# SAM_E54_Xplained_Pro_Target_MCU.net
KiCad netlist of a schematic drawn in Altium Designer
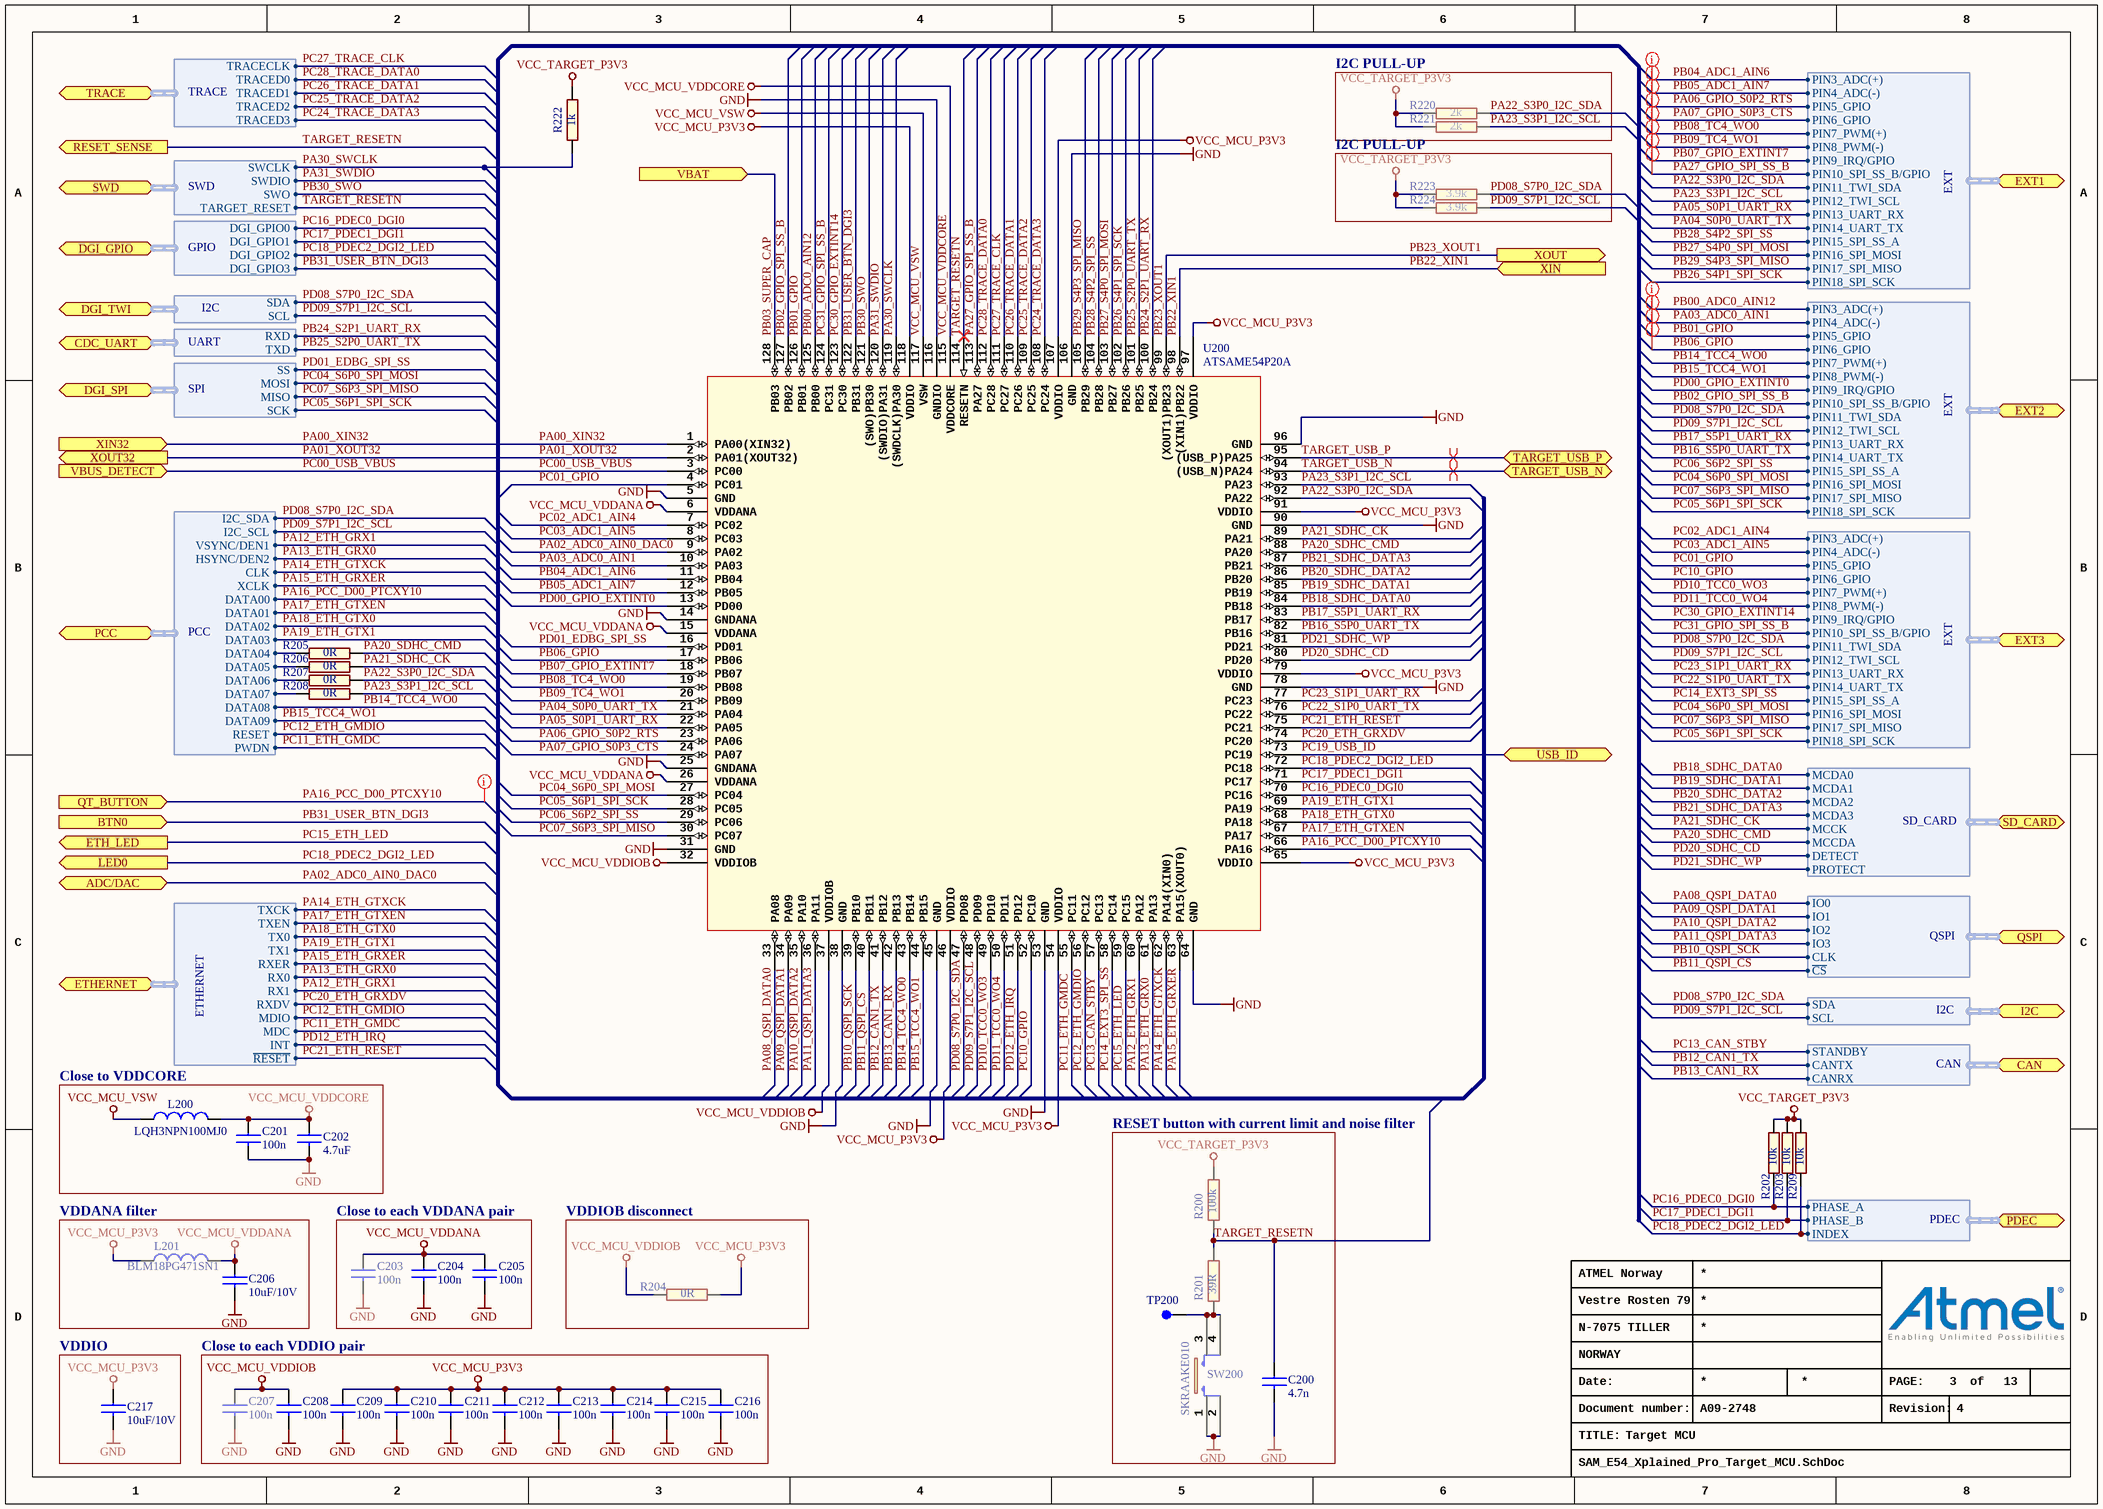
[diagram p0: SAM_E54_Xplained_Pro_Target_MCU.SchDoc]

(export (version "E")
  (design (tool "Eeschema 10.0.6"))
  (components
    (comp (ref "C200")
      (value "4.7n")
      (footprint "AP1-00053")
      (description "Ceramic capacitor, SMD 0402, X7R, 25V, +/-10% (de35287)")
      (fields (field (name "TOLERANCE") "25V, +/-10%") (field (name "MANUFACTURER") "PHYCOMP"))
      (libsource (lib "AltiumDbLib") (part "CAP-NONPOL"))
    )
    (comp (ref "C201")
      (value "100n")
      (footprint "AP1-00053")
      (description "Ceramic capacitor, SMD 0402, X7R, 16V, +/-10%")
      (fields (field (name "TOLERANCE") "16V, +/-10%") (field (name "MANUFACTURER") "Kemet"))
      (libsource (lib "AltiumDbLib") (part "CAP-NONPOL"))
    )
    (comp (ref "C202")
      (value "4.7uF")
      (footprint "AP1-00117")
      (description "Ceramic capacitor, SMD 0603, X5R, 10V, 10% (de31036)")
      (fields (field (name "TOLERANCE") "10%") (field (name "MANUFACTURER") "WALSIN Technology Corporation"))
      (libsource (lib "AltiumDbLib") (part "CAP-NONPOL"))
    )
    (comp (ref "C203")
      (value "100n")
      (footprint "AP1-00053")
      (description "Ceramic capacitor, SMD 0402, X7R, 16V, +/-10%")
      (fields (field (name "TOLERANCE") "16V, +/-10%") (field (name "MANUFACTURER") "Kemet"))
      (libsource (lib "AltiumDbLib") (part "CAP-NONPOL"))
    )
    (comp (ref "C204")
      (value "100n")
      (footprint "AP1-00053")
      (description "Ceramic capacitor, SMD 0402, X7R, 16V, +/-10%")
      (fields (field (name "TOLERANCE") "16V, +/-10%") (field (name "MANUFACTURER") "Kemet"))
      (libsource (lib "AltiumDbLib") (part "CAP-NONPOL"))
    )
    (comp (ref "C205")
      (value "100n")
      (footprint "AP1-00053")
      (description "Ceramic capacitor, SMD 0402, X7R, 16V, +/-10%")
      (fields (field (name "TOLERANCE") "16V, +/-10%") (field (name "MANUFACTURER") "Kemet"))
      (libsource (lib "AltiumDbLib") (part "CAP-NONPOL"))
    )
    (comp (ref "C206")
      (value "10uF/10V")
      (footprint "AP1-00117")
      (description "Ceramic capacitor, SMD 0603, X5R, 10V, 10UF Â± 20%")
      (fields (field (name "MANUFACTURER") "AVX") (field (name "MPN") "0603ZD106MAT2A"))
      (libsource (lib "AltiumDbLib") (part "CAP-NONPOL"))
    )
    (comp (ref "C207")
      (value "100n")
      (footprint "AP1-00053")
      (description "Ceramic capacitor, SMD 0402, X7R, 16V, +/-10%")
      (fields (field (name "TOLERANCE") "16V, +/-10%") (field (name "MANUFACTURER") "Kemet"))
      (libsource (lib "AltiumDbLib") (part "CAP-NONPOL"))
    )
    (comp (ref "C208")
      (value "100n")
      (footprint "AP1-00053")
      (description "Ceramic capacitor, SMD 0402, X7R, 16V, +/-10%")
      (fields (field (name "TOLERANCE") "16V, +/-10%") (field (name "MANUFACTURER") "Kemet"))
      (libsource (lib "AltiumDbLib") (part "CAP-NONPOL"))
    )
    (comp (ref "C209")
      (value "100n")
      (footprint "AP1-00053")
      (description "Ceramic capacitor, SMD 0402, X7R, 16V, +/-10%")
      (fields (field (name "TOLERANCE") "16V, +/-10%") (field (name "MANUFACTURER") "Kemet"))
      (libsource (lib "AltiumDbLib") (part "CAP-NONPOL"))
    )
    (comp (ref "C210")
      (value "100n")
      (footprint "AP1-00053")
      (description "Ceramic capacitor, SMD 0402, X7R, 16V, +/-10%")
      (fields (field (name "TOLERANCE") "16V, +/-10%") (field (name "MANUFACTURER") "Kemet"))
      (libsource (lib "AltiumDbLib") (part "CAP-NONPOL"))
    )
    (comp (ref "C211")
      (value "100n")
      (footprint "AP1-00053")
      (description "Ceramic capacitor, SMD 0402, X7R, 16V, +/-10%")
      (fields (field (name "TOLERANCE") "16V, +/-10%") (field (name "MANUFACTURER") "Kemet"))
      (libsource (lib "AltiumDbLib") (part "CAP-NONPOL"))
    )
    (comp (ref "C212")
      (value "100n")
      (footprint "AP1-00053")
      (description "Ceramic capacitor, SMD 0402, X7R, 16V, +/-10%")
      (fields (field (name "TOLERANCE") "16V, +/-10%") (field (name "MANUFACTURER") "Kemet"))
      (libsource (lib "AltiumDbLib") (part "CAP-NONPOL"))
    )
    (comp (ref "C213")
      (value "100n")
      (footprint "AP1-00053")
      (description "Ceramic capacitor, SMD 0402, X7R, 16V, +/-10%")
      (fields (field (name "TOLERANCE") "16V, +/-10%") (field (name "MANUFACTURER") "Kemet"))
      (libsource (lib "AltiumDbLib") (part "CAP-NONPOL"))
    )
    (comp (ref "C214")
      (value "100n")
      (footprint "AP1-00053")
      (description "Ceramic capacitor, SMD 0402, X7R, 16V, +/-10%")
      (fields (field (name "TOLERANCE") "16V, +/-10%") (field (name "MANUFACTURER") "Kemet"))
      (libsource (lib "AltiumDbLib") (part "CAP-NONPOL"))
    )
    (comp (ref "C215")
      (value "100n")
      (footprint "AP1-00053")
      (description "Ceramic capacitor, SMD 0402, X7R, 16V, +/-10%")
      (fields (field (name "TOLERANCE") "16V, +/-10%") (field (name "MANUFACTURER") "Kemet"))
      (libsource (lib "AltiumDbLib") (part "CAP-NONPOL"))
    )
    (comp (ref "C216")
      (value "100n")
      (footprint "AP1-00053")
      (description "Ceramic capacitor, SMD 0402, X7R, 16V, +/-10%")
      (fields (field (name "TOLERANCE") "16V, +/-10%") (field (name "MANUFACTURER") "Kemet"))
      (libsource (lib "AltiumDbLib") (part "CAP-NONPOL"))
    )
    (comp (ref "C217")
      (value "10uF/10V")
      (footprint "AP1-00117")
      (description "Ceramic capacitor, SMD 0603, X5R, 10V, 10UF Â± 20%")
      (fields (field (name "MANUFACTURER") "AVX") (field (name "MPN") "0603ZD106MAT2A"))
      (libsource (lib "AltiumDbLib") (part "CAP-NONPOL"))
    )
    (comp (ref "L200")
      (value "LQH3NPN100MJ0")
      (footprint "AP3-00115")
      (description "10uH power inductor, Isat = 560mA , Itemp = 710mA, Rdc = 0.360ohm")
      (fields (field (name "TOLERANCE") "Â±20%") (field (name "MANUFACTURER") "Murata"))
      (libsource (lib "AltiumDbLib") (part "INDUCTOR"))
    )
    (comp (ref "L201")
      (value "BLM18PG471SN1")
      (footprint "AP3-00005")
      (description "SMD RF inductor 0603. Z=470Ohm (@100MHz), Max R(dc)=0.65Ohm, Max current=1A")
      (fields (field (name "MANUFACTURER") "Murata"))
      (libsource (lib "AltiumDbLib") (part "INDUCTOR"))
    )
    (comp (ref "R200")
      (value "100k")
      (footprint "AP2-00011")
      (description "Thick film resistor, SMD 0402, 1/16W, 1%")
      (fields (field (name "TOLERANCE") "1 %") (field (name "MANUFACTURER") "ASJ"))
      (libsource (lib "AltiumDbLib") (part "R2"))
    )
    (comp (ref "R201")
      (value "39R")
      (footprint "AP2-00011")
      (description "Thick film resistor, SMD 0402, 1/16W, 1%")
      (fields (field (name "TOLERANCE") "1 %") (field (name "MANUFACTURER") "ASJ"))
      (libsource (lib "") (part "R2_3"))
    )
    (comp (ref "R202")
      (value "10k")
      (footprint "AP2-00011")
      (description "Thick film resistor, SMD 0402, 1/16W, 1%")
      (fields (field (name "TOLERANCE") "1 %") (field (name "MANUFACTURER") "vishay"))
      (libsource (lib "AltiumDbLib") (part "R2"))
    )
    (comp (ref "R203")
      (value "10k")
      (footprint "AP2-00011")
      (description "Thick film resistor, SMD 0402, 1/16W, 1%")
      (fields (field (name "TOLERANCE") "1 %") (field (name "MANUFACTURER") "vishay"))
      (libsource (lib "") (part "R2_2"))
    )
    (comp (ref "R204")
      (value "0R")
      (footprint "AP2-00000")
      (description "RES 0.0 OHM 1/16W 0402 SMD")
      (fields (field (name "TOLERANCE") "1 %") (field (name "MANUFACTURER") "(n/a)"))
      (libsource (lib "") (part "R2_1"))
    )
    (comp (ref "R205")
      (value "0R")
      (footprint "AP2-00000")
      (description "RES 0.0 OHM 1/16W 0402 SMD")
      (fields (field (name "TOLERANCE") "1 %") (field (name "MANUFACTURER") "(n/a)"))
      (libsource (lib "") (part "R2_1"))
    )
    (comp (ref "R206")
      (value "0R")
      (footprint "AP2-00000")
      (description "RES 0.0 OHM 1/16W 0402 SMD")
      (fields (field (name "TOLERANCE") "1 %") (field (name "MANUFACTURER") "(n/a)"))
      (libsource (lib "") (part "R2_1"))
    )
    (comp (ref "R207")
      (value "0R")
      (footprint "AP2-00000")
      (description "RES 0.0 OHM 1/16W 0402 SMD")
      (fields (field (name "TOLERANCE") "1 %") (field (name "MANUFACTURER") "(n/a)"))
      (libsource (lib "") (part "R2_1"))
    )
    (comp (ref "R208")
      (value "0R")
      (footprint "AP2-00000")
      (description "RES 0.0 OHM 1/16W 0402 SMD")
      (fields (field (name "TOLERANCE") "1 %") (field (name "MANUFACTURER") "(n/a)"))
      (libsource (lib "") (part "R2_1"))
    )
    (comp (ref "R209")
      (value "10k")
      (footprint "AP2-00011")
      (description "Thick film resistor, SMD 0402, 1/16W, 1%")
      (fields (field (name "TOLERANCE") "1 %") (field (name "MANUFACTURER") "vishay"))
      (libsource (lib "") (part "R2_2"))
    )
    (comp (ref "R220")
      (value "2k")
      (footprint "AP2-00011")
      (description "Thick film resistor, SMD 0402, 1/16W, 1%")
      (fields (field (name "TOLERANCE") "1 %"))
      (libsource (lib "") (part "R2_1"))
    )
    (comp (ref "R221")
      (value "2k")
      (footprint "AP2-00011")
      (description "Thick film resistor, SMD 0402, 1/16W, 1%")
      (fields (field (name "TOLERANCE") "1 %"))
      (libsource (lib "") (part "R2_1"))
    )
    (comp (ref "R222")
      (value "1k")
      (footprint "AP2-00011")
      (description "Thick film resistor, SMD 0402, 1/16W, 1%")
      (fields (field (name "TOLERANCE") "1 %") (field (name "MANUFACTURER") "ASJ"))
      (libsource (lib "AltiumDbLib") (part "R2"))
    )
    (comp (ref "R223")
      (value "3.9k")
      (footprint "AP2-00011")
      (description "Thick film resistor, SMD 0402, 1/16W, 1%")
      (fields (field (name "TOLERANCE") "1 %"))
      (libsource (lib "") (part "R2_1"))
    )
    (comp (ref "R224")
      (value "3.9k")
      (footprint "AP2-00011")
      (description "Thick film resistor, SMD 0402, 1/16W, 1%")
      (fields (field (name "TOLERANCE") "1 %"))
      (libsource (lib "") (part "R2_1"))
    )
    (comp (ref "SW200")
      (value "SKRAAKE010")
      (footprint "AP8-00137")
      (description "6.2x6.2 mm SMD tact switch, same as A08-0091 but less force is needed")
      (fields (field (name "MANUFACTURER") "ALPS"))
      (libsource (lib "AltiumDbLib") (part "PUSHBUTTON1"))
    )
    (comp (ref "TP200")
      (value "~")
      (footprint "AP8-00010")
      (description "Single SMD testpad")
      (libsource (lib "AltiumDbLib") (part "TESTPOINT"))
    )
    (comp (ref "U200")
      (value "ATSAME54P20A")
      (footprint "AP6-00477")
      (description "Atmel 32-bit RISC MCU")
      (fields (field (name "MANUFACTURER") "ATMEL") (field (name "MPN") "ATSAME54P20A-ANTES"))
      (libsource (lib "AltiumDbLib") (part "SAME54_TQFP128"))
    )
  )
  (nets
    (net (code "15") (name "/DATA04") (class "Default")
      (node (ref "R205") (pin "2") (pinfunction "2_2") (pintype "passive"))
    )
    (net (code "16") (name "/DATA05") (class "Default")
      (node (ref "R206") (pin "2") (pinfunction "2_2") (pintype "passive"))
    )
    (net (code "17") (name "/DATA06") (class "Default")
      (node (ref "R207") (pin "2") (pinfunction "2_2") (pintype "passive"))
    )
    (net (code "18") (name "/DATA07") (class "Default")
      (node (ref "R208") (pin "2") (pinfunction "2_2") (pintype "passive"))
    )
    (net (code "19") (name "/PA00_XIN32") (class "Default")
      (node (ref "U200") (pin "1") (pinfunction "PA00(XIN32)_1") (pintype "bidirectional"))
    )
    (net (code "20") (name "/PA01_XOUT32") (class "Default")
      (node (ref "U200") (pin "2") (pinfunction "PA01(XOUT32)_2") (pintype "bidirectional"))
    )
    (net (code "21") (name "/PA02_ADC0_AIN0_DAC0") (class "Default")
      (node (ref "U200") (pin "9") (pinfunction "PA02_9") (pintype "bidirectional"))
    )
    (net (code "22") (name "/PA03_ADC0_AIN1") (class "Default")
      (node (ref "U200") (pin "10") (pinfunction "PA03_10") (pintype "bidirectional"))
    )
    (net (code "23") (name "/PA04_S0P0_UART_TX") (class "Default")
      (node (ref "U200") (pin "21") (pinfunction "PA04_21") (pintype "bidirectional"))
    )
    (net (code "24") (name "/PA05_S0P1_UART_RX") (class "Default")
      (node (ref "U200") (pin "22") (pinfunction "PA05_22") (pintype "bidirectional"))
    )
    (net (code "25") (name "/PA06_GPIO_S0P2_RTS") (class "Default")
      (node (ref "U200") (pin "23") (pinfunction "PA06_23") (pintype "bidirectional"))
    )
    (net (code "26") (name "/PA07_GPIO_S0P3_CTS") (class "Default")
      (node (ref "U200") (pin "24") (pinfunction "PA07_24") (pintype "bidirectional"))
    )
    (net (code "27") (name "/PA08_QSPI_DATA0") (class "Default")
      (node (ref "U200") (pin "33") (pinfunction "PA08_33") (pintype "bidirectional"))
    )
    (net (code "28") (name "/PA09_QSPI_DATA1") (class "Default")
      (node (ref "U200") (pin "34") (pinfunction "PA09_34") (pintype "bidirectional"))
    )
    (net (code "29") (name "/PA10_QSPI_DATA2") (class "Default")
      (node (ref "U200") (pin "35") (pinfunction "PA10_35") (pintype "bidirectional"))
    )
    (net (code "30") (name "/PA11_QSPI_DATA3") (class "Default")
      (node (ref "U200") (pin "36") (pinfunction "PA11_36") (pintype "bidirectional"))
    )
    (net (code "31") (name "/PA12_ETH_GRX1") (class "Default")
      (node (ref "U200") (pin "60") (pinfunction "PA12_60") (pintype "bidirectional"))
    )
    (net (code "32") (name "/PA13_ETH_GRX0") (class "Default")
      (node (ref "U200") (pin "61") (pinfunction "PA13_61") (pintype "bidirectional"))
    )
    (net (code "33") (name "/PA14_ETH_GTXCK") (class "Default")
      (node (ref "U200") (pin "62") (pinfunction "PA14(XIN0)_62") (pintype "bidirectional"))
    )
    (net (code "34") (name "/PA15_ETH_GRXER") (class "Default")
      (node (ref "U200") (pin "63") (pinfunction "PA15(XOUT0)_63") (pintype "bidirectional"))
    )
    (net (code "35") (name "/PA16_PCC_D00_PTCXY10") (class "Default")
      (node (ref "U200") (pin "66") (pinfunction "PA16_66") (pintype "bidirectional"))
    )
    (net (code "36") (name "/PA17_ETH_GTXEN") (class "Default")
      (node (ref "U200") (pin "67") (pinfunction "PA17_67") (pintype "bidirectional"))
    )
    (net (code "37") (name "/PA18_ETH_GTX0") (class "Default")
      (node (ref "U200") (pin "68") (pinfunction "PA18_68") (pintype "bidirectional"))
    )
    (net (code "38") (name "/PA19_ETH_GTX1") (class "Default")
      (node (ref "U200") (pin "69") (pinfunction "PA19_69") (pintype "bidirectional"))
    )
    (net (code "39") (name "/PA20_SDHC_CMD") (class "Default")
      (node (ref "R205") (pin "1") (pinfunction "1_1") (pintype "passive"))
      (node (ref "U200") (pin "88") (pinfunction "PA20_88") (pintype "bidirectional"))
    )
    (net (code "40") (name "/PA21_SDHC_CK") (class "Default")
      (node (ref "R206") (pin "1") (pinfunction "1_1") (pintype "passive"))
      (node (ref "U200") (pin "89") (pinfunction "PA21_89") (pintype "bidirectional"))
    )
    (net (code "41") (name "/PA22_S3P0_I2C_SDA") (class "Default")
      (node (ref "R207") (pin "1") (pinfunction "1_1") (pintype "passive"))
      (node (ref "R220") (pin "1") (pinfunction "1_1") (pintype "passive"))
      (node (ref "U200") (pin "92") (pinfunction "PA22_92") (pintype "bidirectional"))
    )
    (net (code "42") (name "/PA23_S3P1_I2C_SCL") (class "Default")
      (node (ref "R208") (pin "1") (pinfunction "1_1") (pintype "passive"))
      (node (ref "R221") (pin "1") (pinfunction "1_1") (pintype "passive"))
      (node (ref "U200") (pin "93") (pinfunction "PA23_93") (pintype "bidirectional"))
    )
    (net (code "43") (name "/PA27_GPIO_SPI_SS_B") (class "Default")
      (node (ref "U200") (pin "113") (pinfunction "PA27_113") (pintype "bidirectional"))
    )
    (net (code "44") (name "/PA30_SWCLK") (class "Default")
      (node (ref "R222") (pin "1") (pinfunction "1_1") (pintype "passive"))
      (node (ref "U200") (pin "119") (pinfunction "(SWDCLK)PA30_119") (pintype "bidirectional"))
    )
    (net (code "45") (name "/PA31_SWDIO") (class "Default")
      (node (ref "U200") (pin "120") (pinfunction "(SWDIO)PA31_120") (pintype "bidirectional"))
    )
    (net (code "46") (name "/PB00_ADC0_AIN12") (class "Default")
      (node (ref "U200") (pin "125") (pinfunction "PB00_125") (pintype "bidirectional"))
    )
    (net (code "47") (name "/PB01_GPIO") (class "Default")
      (node (ref "U200") (pin "126") (pinfunction "PB01_126") (pintype "bidirectional"))
    )
    (net (code "48") (name "/PB02_GPIO_SPI_SS_B") (class "Default")
      (node (ref "U200") (pin "127") (pinfunction "PB02_127") (pintype "bidirectional"))
    )
    (net (code "49") (name "/PB03_SUPER_CAP") (class "Default")
      (node (ref "U200") (pin "128") (pinfunction "PB03_128") (pintype "bidirectional"))
    )
    (net (code "50") (name "/PB04_ADC1_AIN6") (class "Default")
      (node (ref "U200") (pin "11") (pinfunction "PB04_11") (pintype "bidirectional"))
    )
    (net (code "51") (name "/PB05_ADC1_AIN7") (class "Default")
      (node (ref "U200") (pin "12") (pinfunction "PB05_12") (pintype "bidirectional"))
    )
    (net (code "52") (name "/PB06_GPIO") (class "Default")
      (node (ref "U200") (pin "17") (pinfunction "PB06_17") (pintype "bidirectional"))
    )
    (net (code "53") (name "/PB07_GPIO_EXTINT7") (class "Default")
      (node (ref "U200") (pin "18") (pinfunction "PB07_18") (pintype "bidirectional"))
    )
    (net (code "54") (name "/PB08_TC4_WO0") (class "Default")
      (node (ref "U200") (pin "19") (pinfunction "PB08_19") (pintype "bidirectional"))
    )
    (net (code "55") (name "/PB09_TC4_WO1") (class "Default")
      (node (ref "U200") (pin "20") (pinfunction "PB09_20") (pintype "bidirectional"))
    )
    (net (code "56") (name "/PB10_QSPI_SCK") (class "Default")
      (node (ref "U200") (pin "39") (pinfunction "PB10_39") (pintype "bidirectional"))
    )
    (net (code "57") (name "/PB11_QSPI_CS") (class "Default")
      (node (ref "U200") (pin "40") (pinfunction "PB11_40") (pintype "bidirectional"))
    )
    (net (code "58") (name "/PB12_CAN1_TX") (class "Default")
      (node (ref "U200") (pin "41") (pinfunction "PB12_41") (pintype "bidirectional"))
    )
    (net (code "59") (name "/PB13_CAN1_RX") (class "Default")
      (node (ref "U200") (pin "42") (pinfunction "PB13_42") (pintype "bidirectional"))
    )
    (net (code "60") (name "/PB14_TCC4_WO0") (class "Default")
      (node (ref "U200") (pin "43") (pinfunction "PB14_43") (pintype "bidirectional"))
    )
    (net (code "61") (name "/PB15_TCC4_WO1") (class "Default")
      (node (ref "U200") (pin "44") (pinfunction "PB15_44") (pintype "bidirectional"))
    )
    (net (code "62") (name "/PB16_S5P0_UART_TX") (class "Default")
      (node (ref "U200") (pin "82") (pinfunction "PB16_82") (pintype "bidirectional"))
    )
    (net (code "63") (name "/PB17_S5P1_UART_RX") (class "Default")
      (node (ref "U200") (pin "83") (pinfunction "PB17_83") (pintype "bidirectional"))
    )
    (net (code "64") (name "/PB18_SDHC_DATA0") (class "Default")
      (node (ref "U200") (pin "84") (pinfunction "PB18_84") (pintype "bidirectional"))
    )
    (net (code "65") (name "/PB19_SDHC_DATA1") (class "Default")
      (node (ref "U200") (pin "85") (pinfunction "PB19_85") (pintype "bidirectional"))
    )
    (net (code "66") (name "/PB20_SDHC_DATA2") (class "Default")
      (node (ref "U200") (pin "86") (pinfunction "PB20_86") (pintype "bidirectional"))
    )
    (net (code "67") (name "/PB21_SDHC_DATA3") (class "Default")
      (node (ref "U200") (pin "87") (pinfunction "PB21_87") (pintype "bidirectional"))
    )
    (net (code "68") (name "/PB22_XIN1") (class "Default")
      (node (ref "U200") (pin "98") (pinfunction "(XIN1)PB22_98") (pintype "bidirectional"))
    )
    (net (code "69") (name "/PB23_XOUT1") (class "Default")
      (node (ref "U200") (pin "99") (pinfunction "(XOUT1)PB23_99") (pintype "bidirectional"))
    )
    (net (code "70") (name "/PB24_S2P1_UART_RX") (class "Default")
      (node (ref "U200") (pin "100") (pinfunction "PB24_100") (pintype "bidirectional"))
    )
    (net (code "71") (name "/PB25_S2P0_UART_TX") (class "Default")
      (node (ref "U200") (pin "101") (pinfunction "PB25_101") (pintype "bidirectional"))
    )
    (net (code "72") (name "/PB26_S4P1_SPI_SCK") (class "Default")
      (node (ref "U200") (pin "102") (pinfunction "PB26_102") (pintype "bidirectional"))
    )
    (net (code "73") (name "/PB27_S4P0_SPI_MOSI") (class "Default")
      (node (ref "U200") (pin "103") (pinfunction "PB27_103") (pintype "bidirectional"))
    )
    (net (code "74") (name "/PB28_S4P2_SPI_SS") (class "Default")
      (node (ref "U200") (pin "104") (pinfunction "PB28_104") (pintype "bidirectional"))
    )
    (net (code "75") (name "/PB29_S4P3_SPI_MISO") (class "Default")
      (node (ref "U200") (pin "105") (pinfunction "PB29_105") (pintype "bidirectional"))
    )
    (net (code "76") (name "/PB30_SWO") (class "Default")
      (node (ref "U200") (pin "121") (pinfunction "(SWO)PB30_121") (pintype "bidirectional"))
    )
    (net (code "77") (name "/PB31_USER_BTN_DGI3") (class "Default")
      (node (ref "U200") (pin "122") (pinfunction "PB31_122") (pintype "bidirectional"))
    )
    (net (code "78") (name "/PC00_USB_VBUS") (class "Default")
      (node (ref "U200") (pin "3") (pinfunction "PC00_3") (pintype "bidirectional"))
    )
    (net (code "79") (name "/PC01_GPIO") (class "Default")
      (node (ref "U200") (pin "4") (pinfunction "PC01_4") (pintype "bidirectional"))
    )
    (net (code "80") (name "/PC02_ADC1_AIN4") (class "Default")
      (node (ref "U200") (pin "7") (pinfunction "PC02_7") (pintype "bidirectional"))
    )
    (net (code "81") (name "/PC03_ADC1_AIN5") (class "Default")
      (node (ref "U200") (pin "8") (pinfunction "PC03_8") (pintype "bidirectional"))
    )
    (net (code "82") (name "/PC04_S6P0_SPI_MOSI") (class "Default")
      (node (ref "U200") (pin "27") (pinfunction "PC04_27") (pintype "bidirectional"))
    )
    (net (code "83") (name "/PC05_S6P1_SPI_SCK") (class "Default")
      (node (ref "U200") (pin "28") (pinfunction "PC05_28") (pintype "bidirectional"))
    )
    (net (code "84") (name "/PC06_S6P2_SPI_SS") (class "Default")
      (node (ref "U200") (pin "29") (pinfunction "PC06_29") (pintype "bidirectional"))
    )
    (net (code "85") (name "/PC07_S6P3_SPI_MISO") (class "Default")
      (node (ref "U200") (pin "30") (pinfunction "PC07_30") (pintype "bidirectional"))
    )
    (net (code "86") (name "/PC10_GPIO") (class "Default")
      (node (ref "U200") (pin "52") (pinfunction "PC10_52") (pintype "bidirectional"))
    )
    (net (code "87") (name "/PC11_ETH_GMDC") (class "Default")
      (node (ref "U200") (pin "55") (pinfunction "PC11_55") (pintype "bidirectional"))
    )
    (net (code "88") (name "/PC12_ETH_GMDIO") (class "Default")
      (node (ref "U200") (pin "56") (pinfunction "PC12_56") (pintype "bidirectional"))
    )
    (net (code "89") (name "/PC13_CAN_STBY") (class "Default")
      (node (ref "U200") (pin "57") (pinfunction "PC13_57") (pintype "bidirectional"))
    )
    (net (code "90") (name "/PC14_EXT3_SPI_SS") (class "Default")
      (node (ref "U200") (pin "58") (pinfunction "PC14_58") (pintype "bidirectional"))
    )
    (net (code "91") (name "/PC15_ETH_LED") (class "Default")
      (node (ref "U200") (pin "59") (pinfunction "PC15_59") (pintype "bidirectional"))
    )
    (net (code "92") (name "/PC16_PDEC0_DGI0") (class "Default")
      (node (ref "R202") (pin "1") (pinfunction "1_1") (pintype "passive"))
      (node (ref "U200") (pin "70") (pinfunction "PC16_70") (pintype "bidirectional"))
    )
    (net (code "93") (name "/PC17_PDEC1_DGI1") (class "Default")
      (node (ref "R203") (pin "2") (pinfunction "2_2") (pintype "passive"))
      (node (ref "U200") (pin "71") (pinfunction "PC17_71") (pintype "bidirectional"))
    )
    (net (code "94") (name "/PC18_PDEC2_DGI2_LED") (class "Default")
      (node (ref "R209") (pin "2") (pinfunction "2_2") (pintype "passive"))
      (node (ref "U200") (pin "72") (pinfunction "PC18_72") (pintype "bidirectional"))
    )
    (net (code "95") (name "/PC19_USB_ID") (class "Default")
      (node (ref "U200") (pin "73") (pinfunction "PC19_73") (pintype "bidirectional"))
    )
    (net (code "96") (name "/PC20_ETH_GRXDV") (class "Default")
      (node (ref "U200") (pin "74") (pinfunction "PC20_74") (pintype "bidirectional"))
    )
    (net (code "97") (name "/PC21_ETH_RESET") (class "Default")
      (node (ref "U200") (pin "75") (pinfunction "PC21_75") (pintype "bidirectional"))
    )
    (net (code "98") (name "/PC22_S1P0_UART_TX") (class "Default")
      (node (ref "U200") (pin "76") (pinfunction "PC22_76") (pintype "bidirectional"))
    )
    (net (code "99") (name "/PC23_S1P1_UART_RX") (class "Default")
      (node (ref "U200") (pin "77") (pinfunction "PC23_77") (pintype "bidirectional"))
    )
    (net (code "100") (name "/PC24_TRACE_DATA3") (class "Default")
      (node (ref "U200") (pin "108") (pinfunction "PC24_108") (pintype "bidirectional"))
    )
    (net (code "101") (name "/PC25_TRACE_DATA2") (class "Default")
      (node (ref "U200") (pin "109") (pinfunction "PC25_109") (pintype "bidirectional"))
    )
    (net (code "102") (name "/PC26_TRACE_DATA1") (class "Default")
      (node (ref "U200") (pin "110") (pinfunction "PC26_110") (pintype "bidirectional"))
    )
    (net (code "103") (name "/PC27_TRACE_CLK") (class "Default")
      (node (ref "U200") (pin "111") (pinfunction "PC27_111") (pintype "bidirectional"))
    )
    (net (code "104") (name "/PC28_TRACE_DATA0") (class "Default")
      (node (ref "U200") (pin "112") (pinfunction "PC28_112") (pintype "bidirectional"))
    )
    (net (code "105") (name "/PC30_GPIO_EXTINT14") (class "Default")
      (node (ref "U200") (pin "123") (pinfunction "PC30_123") (pintype "bidirectional"))
    )
    (net (code "106") (name "/PC31_GPIO_SPI_SS_B") (class "Default")
      (node (ref "U200") (pin "124") (pinfunction "PC31_124") (pintype "bidirectional"))
    )
    (net (code "107") (name "/PD00_GPIO_EXTINT0") (class "Default")
      (node (ref "U200") (pin "13") (pinfunction "PD00_13") (pintype "bidirectional"))
    )
    (net (code "108") (name "/PD01_EDBG_SPI_SS") (class "Default")
      (node (ref "U200") (pin "16") (pinfunction "PD01_16") (pintype "bidirectional"))
    )
    (net (code "109") (name "/PD08_S7P0_I2C_SDA") (class "Default")
      (node (ref "R223") (pin "1") (pinfunction "1_1") (pintype "passive"))
      (node (ref "U200") (pin "47") (pinfunction "PD08_47") (pintype "bidirectional"))
    )
    (net (code "110") (name "/PD09_S7P1_I2C_SCL") (class "Default")
      (node (ref "R224") (pin "1") (pinfunction "1_1") (pintype "passive"))
      (node (ref "U200") (pin "48") (pinfunction "PD09_48") (pintype "bidirectional"))
    )
    (net (code "111") (name "/PD10_TCC0_WO3") (class "Default")
      (node (ref "U200") (pin "49") (pinfunction "PD10_49") (pintype "bidirectional"))
    )
    (net (code "112") (name "/PD11_TCC0_WO4") (class "Default")
      (node (ref "U200") (pin "50") (pinfunction "PD11_50") (pintype "bidirectional"))
    )
    (net (code "113") (name "/PD12_ETH_IRQ") (class "Default")
      (node (ref "U200") (pin "51") (pinfunction "PD12_51") (pintype "bidirectional"))
    )
    (net (code "114") (name "/PD20_SDHC_CD") (class "Default")
      (node (ref "U200") (pin "80") (pinfunction "PD20_80") (pintype "bidirectional"))
    )
    (net (code "115") (name "/PD21_SDHC_WP") (class "Default")
      (node (ref "U200") (pin "81") (pinfunction "PD21_81") (pintype "bidirectional"))
    )
    (net (code "116") (name "/TARGET_RESETN") (class "Default")
      (node (ref "C200") (pin "1") (pinfunction "1_1") (pintype "passive"))
      (node (ref "R200") (pin "1") (pinfunction "1_1") (pintype "passive"))
      (node (ref "R201") (pin "2") (pinfunction "2_2") (pintype "passive"))
      (node (ref "U200") (pin "114") (pinfunction "RESETN_114") (pintype "input"))
    )
    (net (code "117") (name "/TARGET_USB_N") (class "Default")
      (node (ref "U200") (pin "94") (pinfunction "(USB_N)PA24_94") (pintype "bidirectional"))
    )
    (net (code "118") (name "/TARGET_USB_P") (class "Default")
      (node (ref "U200") (pin "95") (pinfunction "(USB_P)PA25_95") (pintype "bidirectional"))
    )
    (net (code "131") (name "GND") (class "Default")
      (node (ref "C200") (pin "2") (pinfunction "2_2") (pintype "passive"))
      (node (ref "C201") (pin "2") (pinfunction "2_2") (pintype "passive"))
      (node (ref "C202") (pin "2") (pinfunction "2_2") (pintype "passive"))
      (node (ref "C203") (pin "2") (pinfunction "2_2") (pintype "passive"))
      (node (ref "C204") (pin "2") (pinfunction "2_2") (pintype "passive"))
      (node (ref "C205") (pin "2") (pinfunction "2_2") (pintype "passive"))
      (node (ref "C206") (pin "2") (pinfunction "2_2") (pintype "passive"))
      (node (ref "C207") (pin "2") (pinfunction "2_2") (pintype "passive"))
      (node (ref "C208") (pin "2") (pinfunction "2_2") (pintype "passive"))
      (node (ref "C209") (pin "2") (pinfunction "2_2") (pintype "passive"))
      (node (ref "C210") (pin "2") (pinfunction "2_2") (pintype "passive"))
      (node (ref "C211") (pin "2") (pinfunction "2_2") (pintype "passive"))
      (node (ref "C212") (pin "2") (pinfunction "2_2") (pintype "passive"))
      (node (ref "C213") (pin "2") (pinfunction "2_2") (pintype "passive"))
      (node (ref "C214") (pin "2") (pinfunction "2_2") (pintype "passive"))
      (node (ref "C215") (pin "2") (pinfunction "2_2") (pintype "passive"))
      (node (ref "C216") (pin "2") (pinfunction "2_2") (pintype "passive"))
      (node (ref "C217") (pin "2") (pinfunction "2_2") (pintype "passive"))
      (node (ref "SW200") (pin "1") (pinfunction "1_1") (pintype "passive"))
      (node (ref "SW200") (pin "2") (pinfunction "2_2") (pintype "passive"))
      (node (ref "U200") (pin "106") (pinfunction "GND_106") (pintype "power_in"))
      (node (ref "U200") (pin "116") (pinfunction "GNDIO_116") (pintype "power_in"))
      (node (ref "U200") (pin "14") (pinfunction "GNDANA_14") (pintype "power_in"))
      (node (ref "U200") (pin "25") (pinfunction "GNDANA_25") (pintype "power_in"))
      (node (ref "U200") (pin "31") (pinfunction "GND_31") (pintype "power_in"))
      (node (ref "U200") (pin "38") (pinfunction "GND_38") (pintype "power_in"))
      (node (ref "U200") (pin "45") (pinfunction "GND_45") (pintype "power_in"))
      (node (ref "U200") (pin "5") (pinfunction "GND_5") (pintype "power_in"))
      (node (ref "U200") (pin "53") (pinfunction "GND_53") (pintype "power_in"))
      (node (ref "U200") (pin "64") (pinfunction "GND_64") (pintype "power_in"))
      (node (ref "U200") (pin "78") (pinfunction "GND_78") (pintype "power_in"))
      (node (ref "U200") (pin "90") (pinfunction "GND_90") (pintype "power_in"))
      (node (ref "U200") (pin "96") (pinfunction "GND_96") (pintype "power_in"))
    )
    (net (code "132") (name "Net-(R201-Pad1)") (class "Default")
      (node (ref "R201") (pin "1") (pinfunction "1_1") (pintype "passive"))
      (node (ref "SW200") (pin "3") (pinfunction "3_3") (pintype "passive"))
      (node (ref "SW200") (pin "4") (pinfunction "4_4") (pintype "passive"))
      (node (ref "TP200") (pin "1") (pinfunction "1_1") (pintype "passive"))
    )
    (net (code "133") (name "VCC_MCU_P3V3") (class "Default")
      (node (ref "C209") (pin "1") (pinfunction "1_1") (pintype "passive"))
      (node (ref "C210") (pin "1") (pinfunction "1_1") (pintype "passive"))
      (node (ref "C211") (pin "1") (pinfunction "1_1") (pintype "passive"))
      (node (ref "C212") (pin "1") (pinfunction "1_1") (pintype "passive"))
      (node (ref "C213") (pin "1") (pinfunction "1_1") (pintype "passive"))
      (node (ref "C214") (pin "1") (pinfunction "1_1") (pintype "passive"))
      (node (ref "C215") (pin "1") (pinfunction "1_1") (pintype "passive"))
      (node (ref "C216") (pin "1") (pinfunction "1_1") (pintype "passive"))
      (node (ref "C217") (pin "1") (pinfunction "1_1") (pintype "passive"))
      (node (ref "L201") (pin "1") (pinfunction "1_1") (pintype "passive"))
      (node (ref "R204") (pin "1") (pinfunction "1_1") (pintype "passive"))
      (node (ref "U200") (pin "107") (pinfunction "VDDIO_107") (pintype "power_in"))
      (node (ref "U200") (pin "118") (pinfunction "VDDIO_118") (pintype "power_in"))
      (node (ref "U200") (pin "46") (pinfunction "VDDIO_46") (pintype "power_in"))
      (node (ref "U200") (pin "54") (pinfunction "VDDIO_54") (pintype "power_in"))
      (node (ref "U200") (pin "65") (pinfunction "VDDIO_65") (pintype "power_in"))
      (node (ref "U200") (pin "79") (pinfunction "VDDIO_79") (pintype "power_in"))
      (node (ref "U200") (pin "91") (pinfunction "VDDIO_91") (pintype "power_in"))
      (node (ref "U200") (pin "97") (pinfunction "VDDIO_97") (pintype "power_in"))
    )
    (net (code "134") (name "VCC_MCU_VDDANA") (class "Default")
      (node (ref "C203") (pin "1") (pinfunction "1_1") (pintype "passive"))
      (node (ref "C204") (pin "1") (pinfunction "1_1") (pintype "passive"))
      (node (ref "C205") (pin "1") (pinfunction "1_1") (pintype "passive"))
      (node (ref "C206") (pin "1") (pinfunction "1_1") (pintype "passive"))
      (node (ref "L201") (pin "2") (pinfunction "2_2") (pintype "passive"))
      (node (ref "U200") (pin "15") (pinfunction "VDDANA_15") (pintype "power_in"))
      (node (ref "U200") (pin "26") (pinfunction "VDDANA_26") (pintype "power_in"))
      (node (ref "U200") (pin "6") (pinfunction "VDDANA_6") (pintype "power_in"))
    )
    (net (code "135") (name "VCC_MCU_VDDCORE") (class "Default")
      (node (ref "C201") (pin "1") (pinfunction "1_1") (pintype "passive"))
      (node (ref "C202") (pin "1") (pinfunction "1_1") (pintype "passive"))
      (node (ref "L200") (pin "2") (pinfunction "2_2") (pintype "passive"))
      (node (ref "U200") (pin "115") (pinfunction "VDDCORE_115") (pintype "power_in"))
    )
    (net (code "136") (name "VCC_MCU_VDDIOB") (class "Default")
      (node (ref "C207") (pin "1") (pinfunction "1_1") (pintype "passive"))
      (node (ref "C208") (pin "1") (pinfunction "1_1") (pintype "passive"))
      (node (ref "R204") (pin "2") (pinfunction "2_2") (pintype "passive"))
      (node (ref "U200") (pin "32") (pinfunction "VDDIOB_32") (pintype "power_in"))
      (node (ref "U200") (pin "37") (pinfunction "VDDIOB_37") (pintype "power_in"))
    )
    (net (code "137") (name "VCC_MCU_VSW") (class "Default")
      (node (ref "L200") (pin "1") (pinfunction "1_1") (pintype "passive"))
      (node (ref "U200") (pin "117") (pinfunction "VSW_117") (pintype "power_in"))
    )
    (net (code "138") (name "VCC_TARGET_P3V3") (class "Default")
      (node (ref "R200") (pin "2") (pinfunction "2_2") (pintype "passive"))
      (node (ref "R202") (pin "2") (pinfunction "2_2") (pintype "passive"))
      (node (ref "R203") (pin "1") (pinfunction "1_1") (pintype "passive"))
      (node (ref "R209") (pin "1") (pinfunction "1_1") (pintype "passive"))
      (node (ref "R220") (pin "2") (pinfunction "2_2") (pintype "passive"))
      (node (ref "R221") (pin "2") (pinfunction "2_2") (pintype "passive"))
      (node (ref "R222") (pin "2") (pinfunction "2_2") (pintype "passive"))
      (node (ref "R223") (pin "2") (pinfunction "2_2") (pintype "passive"))
      (node (ref "R224") (pin "2") (pinfunction "2_2") (pintype "passive"))
    )
  )
)
